# Ethernet.net
KiCad netlist of a schematic drawn in Altium Designer
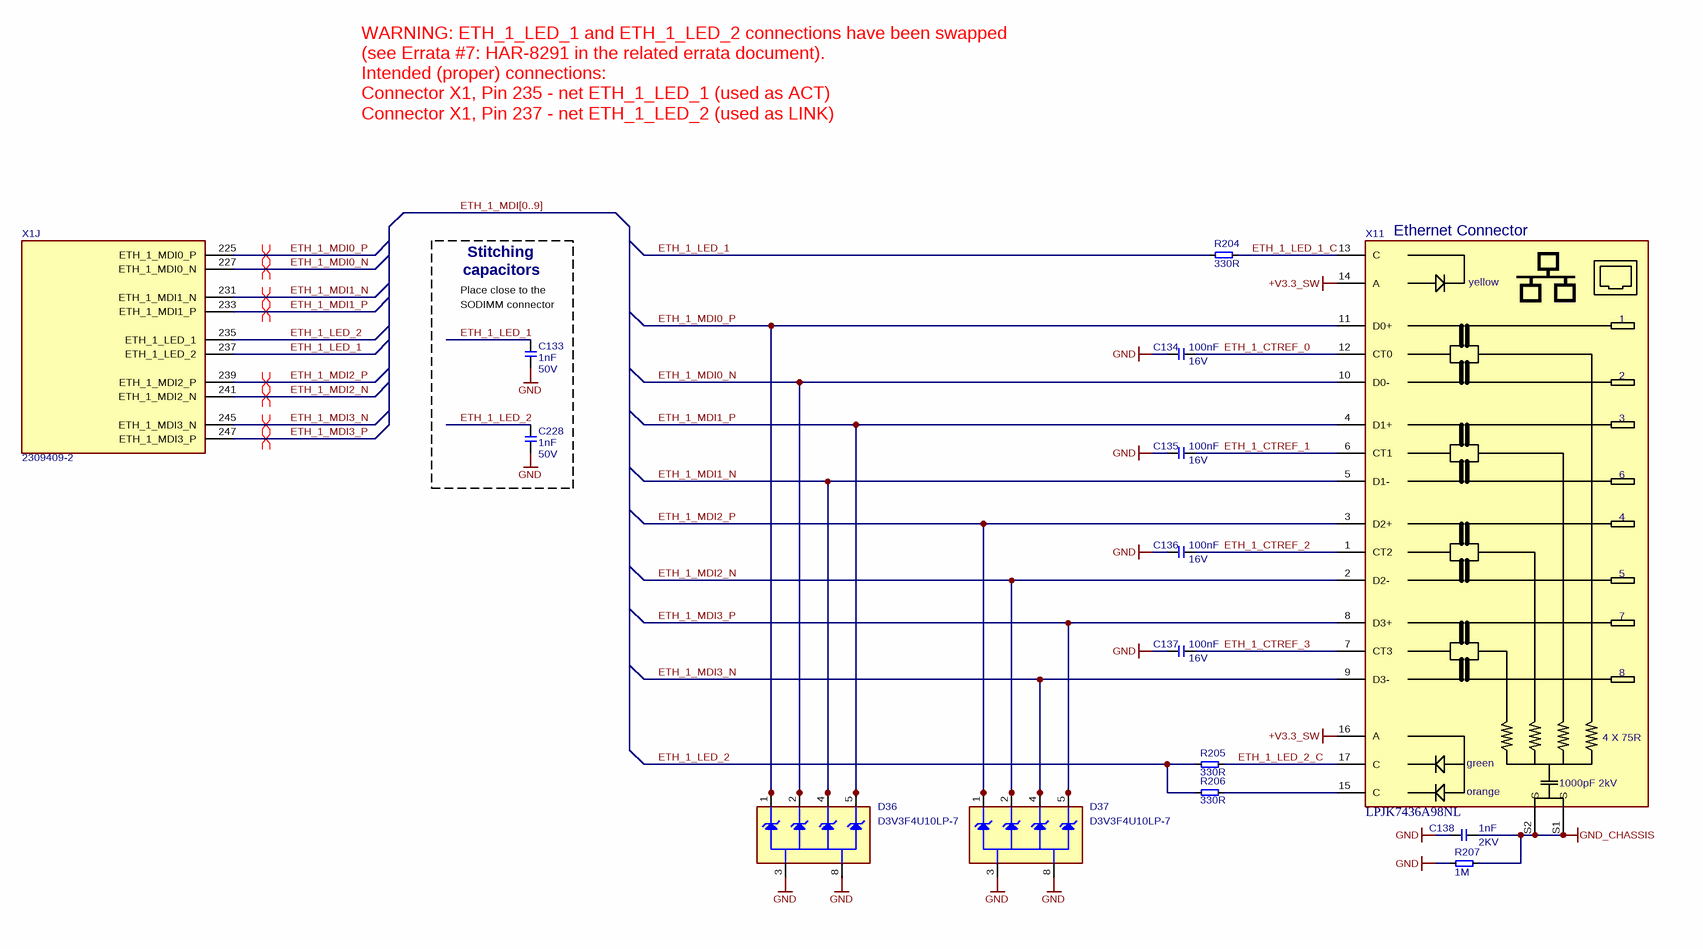
[diagram p0: Ethernet.SchDoc]

(export (version "E")
  (design (tool "Eeschema 10.0.6"))
  (components
    (comp (ref "C133")
      (value "1nF")
      (footprint "CAPC1005X60N")
      (description "Capacitor Ceramic X7R 1nF 50V 10% 0402")
      (fields (field (name "TOLERANCE") "10%") (field (name "RATING") "50V"))
      (libsource (lib "Dahlia Carrier Board") (part "C-X7R-1nF-50V-10%-0402"))
    )
    (comp (ref "C134")
      (value "100nF")
      (footprint "CAPC1005X60N")
      (description "Capacitor Ceramic X7R 100nF 16V 10% 0402")
      (fields (field (name "TOLERANCE") "10%") (field (name "RATING") "16V"))
      (libsource (lib "Dahlia Carrier Board") (part "C-X7R-100nF-16V-10%-0402"))
    )
    (comp (ref "C135")
      (value "100nF")
      (footprint "CAPC1005X60N")
      (description "Capacitor Ceramic X7R 100nF 16V 10% 0402")
      (fields (field (name "TOLERANCE") "10%") (field (name "RATING") "16V"))
      (libsource (lib "Dahlia Carrier Board") (part "C-X7R-100nF-16V-10%-0402"))
    )
    (comp (ref "C136")
      (value "100nF")
      (footprint "CAPC1005X60N")
      (description "Capacitor Ceramic X7R 100nF 16V 10% 0402")
      (fields (field (name "TOLERANCE") "10%") (field (name "RATING") "16V"))
      (libsource (lib "Dahlia Carrier Board") (part "C-X7R-100nF-16V-10%-0402"))
    )
    (comp (ref "C137")
      (value "100nF")
      (footprint "CAPC1005X60N")
      (description "Capacitor Ceramic X7R 100nF 16V 10% 0402")
      (fields (field (name "TOLERANCE") "10%") (field (name "RATING") "16V"))
      (libsource (lib "Dahlia Carrier Board") (part "C-X7R-100nF-16V-10%-0402"))
    )
    (comp (ref "C138")
      (value "1nF")
      (footprint "T_CAPC1206X180N")
      (description "Capacitor Ceramic X7R 1nF 2KV 10% 1206")
      (fields (field (name "TOLERANCE") "10%") (field (name "RATING") "2KV"))
      (libsource (lib "Dahlia Carrier Board") (part "C-X7R-1nF-2KV-10%-1206"))
    )
    (comp (ref "C228")
      (value "1nF")
      (footprint "CAPC1005X60N")
      (description "Capacitor Ceramic X7R 1nF 50V 10% 0402")
      (fields (field (name "TOLERANCE") "10%") (field (name "RATING") "50V"))
      (libsource (lib "Dahlia Carrier Board") (part "C-X7R-1nF-50V-10%-0402"))
    )
    (comp (ref "D36")
      (value "D3V3F4U10LP-7")
      (footprint "D-Diodes-D3V3F4U10LP-7")
      (description "4 CHANNEL LOW CAPACITANCE TVS DIODE ARRAY")
      (fields (field (name "MANUFACTURER PART NO.") "D3V3F4U10LP-7"))
      (libsource (lib "Dahlia Carrier Board") (part "D-Diodes-D3V3F4U10LP-7"))
    )
    (comp (ref "D37")
      (value "D3V3F4U10LP-7")
      (footprint "D-Diodes-D3V3F4U10LP-7")
      (description "4 CHANNEL LOW CAPACITANCE TVS DIODE ARRAY")
      (fields (field (name "MANUFACTURER PART NO.") "D3V3F4U10LP-7"))
      (libsource (lib "Dahlia Carrier Board") (part "D-Diodes-D3V3F4U10LP-7"))
    )
    (comp (ref "R204")
      (value "330R")
      (footprint "RESC1005X40N")
      (description "Resistor 330 ohm 63mW 5% 0402")
      (fields (field (name "TOLERANCE") "5%"))
      (libsource (lib "Dahlia Carrier Board") (part "R-330R-63mW-5%-0402"))
    )
    (comp (ref "R205")
      (value "330R")
      (footprint "RESC1005X40N")
      (description "Resistor 330 ohm 63mW 5% 0402")
      (fields (field (name "TOLERANCE") "5%"))
      (libsource (lib "Dahlia Carrier Board") (part "R-330R-63mW-5%-0402"))
    )
    (comp (ref "R206")
      (value "330R")
      (footprint "RESC1005X40N")
      (description "Resistor 330 ohm 63mW 5% 0402")
      (fields (field (name "TOLERANCE") "5%"))
      (libsource (lib "Dahlia Carrier Board") (part "R-330R-63mW-5%-0402"))
    )
    (comp (ref "R207")
      (value "1M")
      (footprint "RESC3216X75N")
      (description "Resistor 1 Mohm 250mW 5% 1206")
      (fields (field (name "TOLERANCE") "5%"))
      (libsource (lib "Dahlia Carrier Board") (part "R-1M-250mW-5%-1206"))
    )
    (comp (ref "X1")
      (value "2309409-2")
      (footprint "CON-TE-2309409-2-SOLDERABLE-STANDOFFS")
      (description "DDR4 SODIMM Socket, 260 pins, 5.2mm(H), 0.5mm Pitch")
      (libsource (lib "Dahlia Carrier Board") (part "CON-TE-2309409-2"))
    )
    (comp (ref "X11")
      (value "LPJK7436A98NL")
      (footprint "CON-LINK-PP-LPJK7436A98NL")
      (fields (field (name "MANUFACTURER PART NO.") "LPJK7436A98NL"))
      (libsource (lib "Dahlia Carrier Board") (part "CON-ETH-RJ45-1000BaseT"))
    )
  )
  (nets
    (net (code "11") (name "+V3.3_SW") (class "Default")
      (node (ref "X11") (pin "14") (pinfunction "A_14") (pintype "passive"))
      (node (ref "X11") (pin "16") (pinfunction "A_16") (pintype "passive"))
    )
    (net (code "12") (name "/ETH_1_CTREF_0") (class "Default")
      (node (ref "C134") (pin "1") (pinfunction "1_1") (pintype "passive"))
      (node (ref "X11") (pin "12") (pinfunction "CT0_12") (pintype "passive"))
    )
    (net (code "13") (name "/ETH_1_CTREF_1") (class "Default")
      (node (ref "C135") (pin "1") (pinfunction "1_1") (pintype "passive"))
      (node (ref "X11") (pin "6") (pinfunction "CT1_6") (pintype "passive"))
    )
    (net (code "14") (name "/ETH_1_CTREF_2") (class "Default")
      (node (ref "C136") (pin "1") (pinfunction "1_1") (pintype "passive"))
      (node (ref "X11") (pin "1") (pinfunction "CT2_1") (pintype "passive"))
    )
    (net (code "15") (name "/ETH_1_CTREF_3") (class "Default")
      (node (ref "C137") (pin "1") (pinfunction "1_1") (pintype "passive"))
      (node (ref "X11") (pin "7") (pinfunction "CT3_7") (pintype "passive"))
    )
    (net (code "16") (name "/ETH_1_LED_1") (class "Default")
      (node (ref "C133") (pin "2") (pinfunction "2_2") (pintype "passive"))
      (node (ref "R204") (pin "2") (pinfunction "2_2") (pintype "passive"))
      (node (ref "X1") (pin "237") (pinfunction "ETH_1_LED_2_237") (pintype "passive"))
    )
    (net (code "17") (name "/ETH_1_LED_1_C") (class "Default")
      (node (ref "R204") (pin "1") (pinfunction "1_1") (pintype "passive"))
      (node (ref "X11") (pin "13") (pinfunction "C_13") (pintype "passive"))
    )
    (net (code "18") (name "/ETH_1_LED_2") (class "Default")
      (node (ref "C228") (pin "2") (pinfunction "2_2") (pintype "passive"))
      (node (ref "R205") (pin "2") (pinfunction "2_2") (pintype "passive"))
      (node (ref "R206") (pin "2") (pinfunction "2_2") (pintype "passive"))
      (node (ref "X1") (pin "235") (pinfunction "ETH_1_LED_1_235") (pintype "passive"))
    )
    (net (code "19") (name "/ETH_1_LED_2_C") (class "Default")
      (node (ref "R205") (pin "1") (pinfunction "1_1") (pintype "passive"))
      (node (ref "X11") (pin "17") (pinfunction "C_17") (pintype "passive"))
    )
    (net (code "20") (name "/ETH_1_MDI0_N") (class "Default")
      (node (ref "D36") (pin "2") (pinfunction "2_2") (pintype "passive"))
      (node (ref "D36") (pin "9") (pinfunction "9_9") (pintype "passive"))
      (node (ref "X1") (pin "227") (pinfunction "ETH_1_MDI0_N_227") (pintype "passive"))
      (node (ref "X11") (pin "10") (pinfunction "D0-_10") (pintype "passive"))
    )
    (net (code "21") (name "/ETH_1_MDI0_P") (class "Default")
      (node (ref "D36") (pin "1") (pinfunction "1_1") (pintype "passive"))
      (node (ref "D36") (pin "10") (pinfunction "10_10") (pintype "passive"))
      (node (ref "X1") (pin "225") (pinfunction "ETH_1_MDI0_P_225") (pintype "power_in"))
      (node (ref "X11") (pin "11") (pinfunction "D0+_11") (pintype "passive"))
    )
    (net (code "22") (name "/ETH_1_MDI1_N") (class "Default")
      (node (ref "D36") (pin "4") (pinfunction "4_4") (pintype "passive"))
      (node (ref "D36") (pin "7") (pinfunction "7_7") (pintype "passive"))
      (node (ref "X1") (pin "231") (pinfunction "ETH_1_MDI1_N_231") (pintype "power_in"))
      (node (ref "X11") (pin "5") (pinfunction "D1-_5") (pintype "passive"))
    )
    (net (code "23") (name "/ETH_1_MDI1_P") (class "Default")
      (node (ref "D36") (pin "5") (pinfunction "5_5") (pintype "passive"))
      (node (ref "D36") (pin "6") (pinfunction "6_6") (pintype "passive"))
      (node (ref "X1") (pin "233") (pinfunction "ETH_1_MDI1_P_233") (pintype "passive"))
      (node (ref "X11") (pin "4") (pinfunction "D1+_4") (pintype "passive"))
    )
    (net (code "24") (name "/ETH_1_MDI2_N") (class "Default")
      (node (ref "D37") (pin "2") (pinfunction "2_2") (pintype "passive"))
      (node (ref "D37") (pin "9") (pinfunction "9_9") (pintype "passive"))
      (node (ref "X1") (pin "241") (pinfunction "ETH_1_MDI2_N_241") (pintype "passive"))
      (node (ref "X11") (pin "2") (pinfunction "D2-_2") (pintype "passive"))
    )
    (net (code "25") (name "/ETH_1_MDI2_P") (class "Default")
      (node (ref "D37") (pin "1") (pinfunction "1_1") (pintype "passive"))
      (node (ref "D37") (pin "10") (pinfunction "10_10") (pintype "passive"))
      (node (ref "X1") (pin "239") (pinfunction "ETH_1_MDI2_P_239") (pintype "passive"))
      (node (ref "X11") (pin "3") (pinfunction "D2+_3") (pintype "passive"))
    )
    (net (code "26") (name "/ETH_1_MDI3_N") (class "Default")
      (node (ref "D37") (pin "4") (pinfunction "4_4") (pintype "passive"))
      (node (ref "D37") (pin "7") (pinfunction "7_7") (pintype "passive"))
      (node (ref "X1") (pin "245") (pinfunction "ETH_1_MDI3_N_245") (pintype "passive"))
      (node (ref "X11") (pin "9") (pinfunction "D3-_9") (pintype "passive"))
    )
    (net (code "27") (name "/ETH_1_MDI3_P") (class "Default")
      (node (ref "D37") (pin "5") (pinfunction "5_5") (pintype "passive"))
      (node (ref "D37") (pin "6") (pinfunction "6_6") (pintype "passive"))
      (node (ref "X1") (pin "247") (pinfunction "ETH_1_MDI3_P_247") (pintype "passive"))
      (node (ref "X11") (pin "8") (pinfunction "D3+_8") (pintype "passive"))
    )
    (net (code "29") (name "GND") (class "Default")
      (node (ref "C133") (pin "1") (pinfunction "1_1") (pintype "passive"))
      (node (ref "C134") (pin "2") (pinfunction "2_2") (pintype "passive"))
      (node (ref "C135") (pin "2") (pinfunction "2_2") (pintype "passive"))
      (node (ref "C136") (pin "2") (pinfunction "2_2") (pintype "passive"))
      (node (ref "C137") (pin "2") (pinfunction "2_2") (pintype "passive"))
      (node (ref "C138") (pin "1") (pinfunction "1_1") (pintype "passive"))
      (node (ref "C228") (pin "1") (pinfunction "1_1") (pintype "passive"))
      (node (ref "D36") (pin "3") (pinfunction "3_3") (pintype "power_in"))
      (node (ref "D36") (pin "8") (pinfunction "8_8") (pintype "power_in"))
      (node (ref "D37") (pin "3") (pinfunction "3_3") (pintype "power_in"))
      (node (ref "D37") (pin "8") (pinfunction "8_8") (pintype "power_in"))
      (node (ref "R207") (pin "2") (pinfunction "2_2") (pintype "passive"))
    )
    (net (code "30") (name "GND_CHASSIS") (class "Default")
      (node (ref "C138") (pin "2") (pinfunction "2_2") (pintype "passive"))
      (node (ref "R207") (pin "1") (pinfunction "1_1") (pintype "passive"))
      (node (ref "X11") (pin "S1") (pinfunction "S_S1") (pintype "passive"))
      (node (ref "X11") (pin "S2") (pinfunction "S_S2") (pintype "passive"))
    )
    (net (code "31") (name "Net-(R206-Pad1)") (class "Default")
      (node (ref "R206") (pin "1") (pinfunction "1_1") (pintype "passive"))
      (node (ref "X11") (pin "15") (pinfunction "C_15") (pintype "passive"))
    )
  )
)
